# R107A.net
KiCad netlist of a schematic drawn in EAGLE
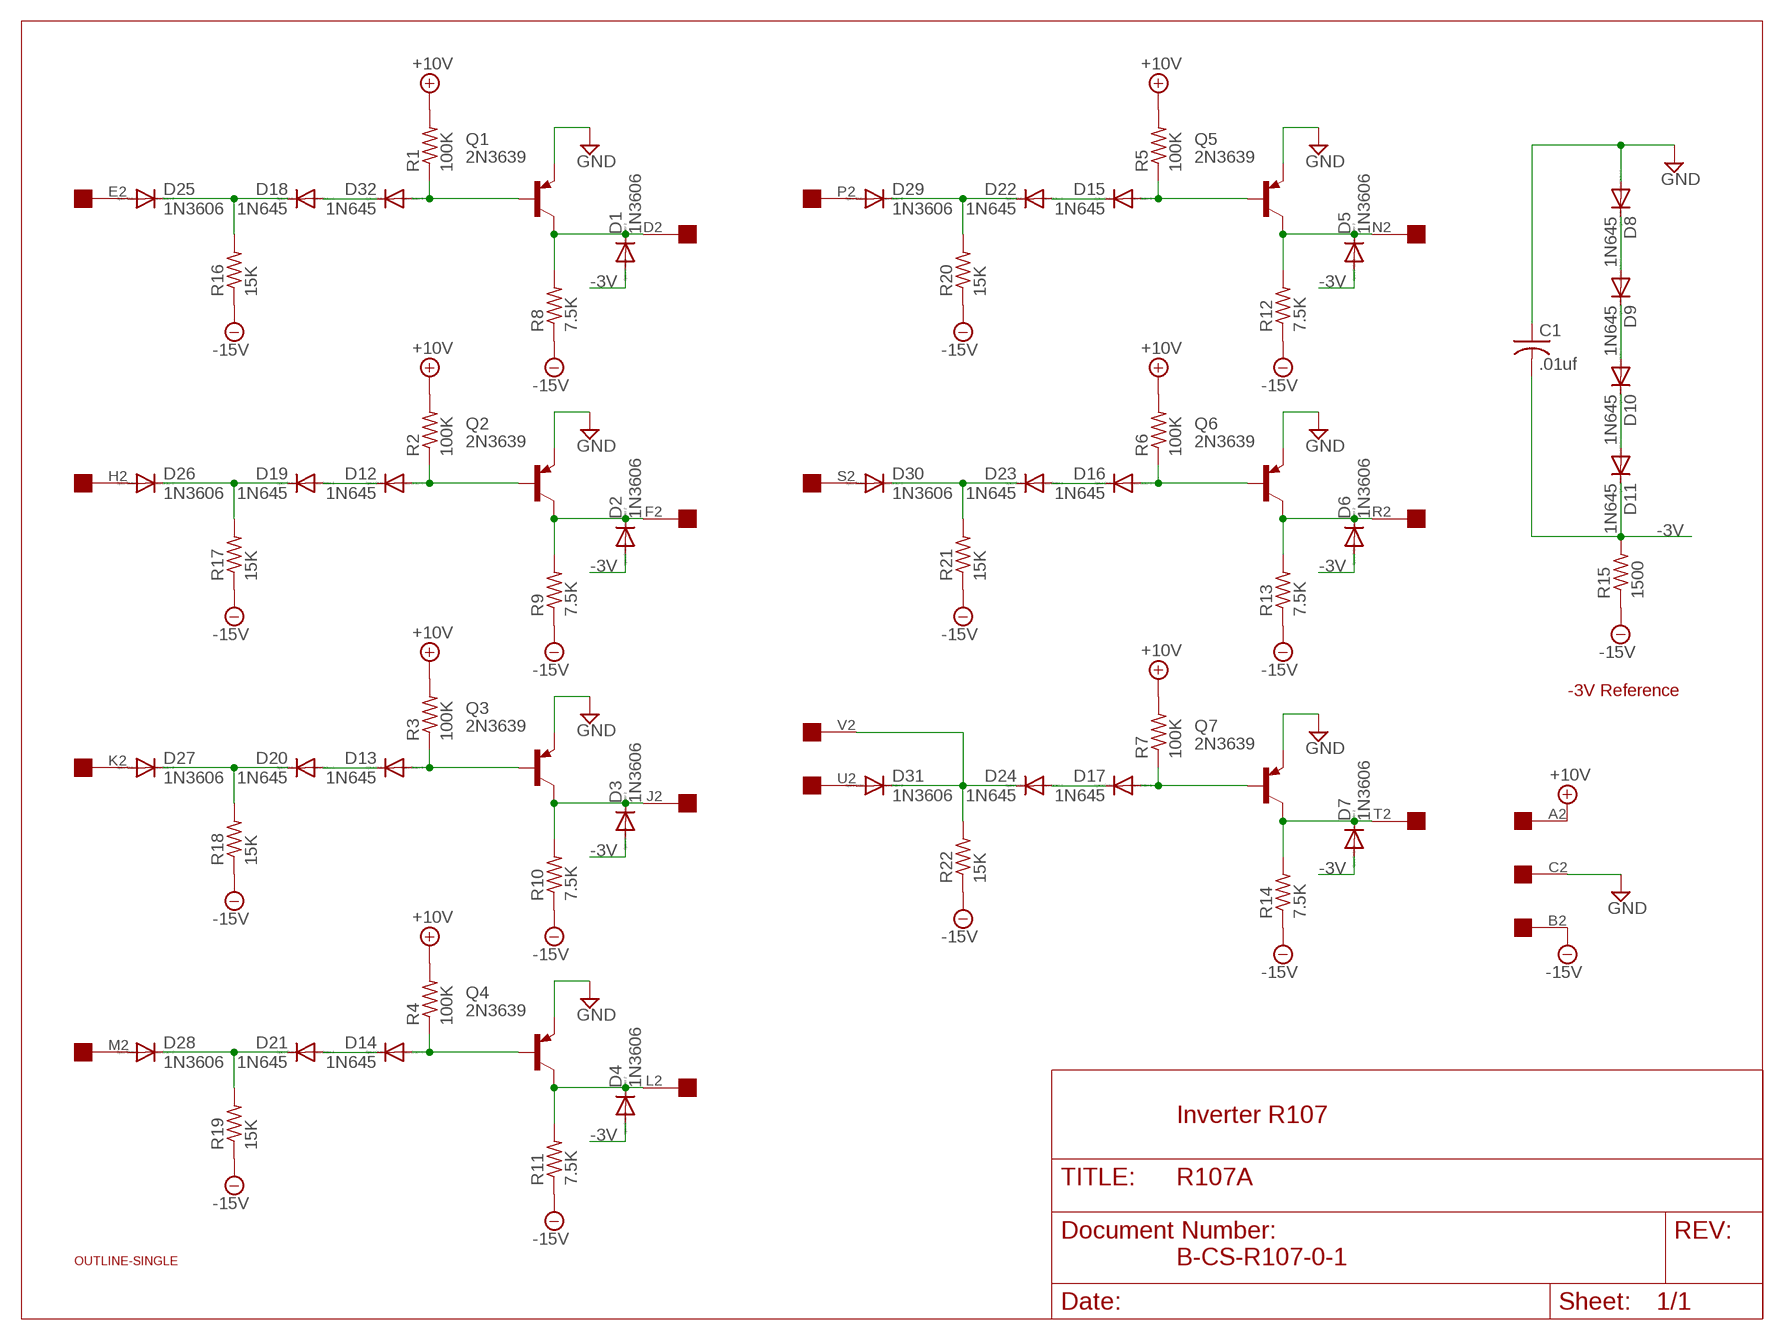
[diagram p0: schematic, sheet 1]

(export (version "E")
  (design (tool "Eeschema 10.0.6"))
  (components
    (comp (ref "C1")
      (value ".01uf")
      (footprint "eagle-import:C050-025X075")
      (libsource (lib "eagle-import") (part "C-US050-025X075"))
    )
    (comp (ref "D1")
      (value "1N3606")
      (footprint "eagle-import:DO35-10")
      (libsource (lib "eagle-import") (part "1N4148DO35-10"))
    )
    (comp (ref "D2")
      (value "1N3606")
      (footprint "eagle-import:DO35-10")
      (libsource (lib "eagle-import") (part "1N4148DO35-10"))
    )
    (comp (ref "D3")
      (value "1N3606")
      (footprint "eagle-import:DO35-10")
      (libsource (lib "eagle-import") (part "1N4148DO35-10"))
    )
    (comp (ref "D4")
      (value "1N3606")
      (footprint "eagle-import:DO35-10")
      (libsource (lib "eagle-import") (part "1N4148DO35-10"))
    )
    (comp (ref "D5")
      (value "1N3606")
      (footprint "eagle-import:DO35-10")
      (libsource (lib "eagle-import") (part "1N4148DO35-10"))
    )
    (comp (ref "D6")
      (value "1N3606")
      (footprint "eagle-import:DO35-10")
      (libsource (lib "eagle-import") (part "1N4148DO35-10"))
    )
    (comp (ref "D7")
      (value "1N3606")
      (footprint "eagle-import:DO35-10")
      (libsource (lib "eagle-import") (part "1N4148DO35-10"))
    )
    (comp (ref "D8")
      (value "1N645")
      (footprint "eagle-import:DO35-10")
      (libsource (lib "eagle-import") (part "1N4148DO35-10"))
    )
    (comp (ref "D9")
      (value "1N645")
      (footprint "eagle-import:DO35-10")
      (libsource (lib "eagle-import") (part "1N4148DO35-10"))
    )
    (comp (ref "D10")
      (value "1N645")
      (footprint "eagle-import:DO35-10")
      (libsource (lib "eagle-import") (part "1N4148DO35-10"))
    )
    (comp (ref "D11")
      (value "1N645")
      (footprint "eagle-import:DO35-10")
      (libsource (lib "eagle-import") (part "1N4148DO35-10"))
    )
    (comp (ref "D12")
      (value "1N645")
      (footprint "eagle-import:DO35-10")
      (libsource (lib "eagle-import") (part "1N4148DO35-10"))
    )
    (comp (ref "D13")
      (value "1N645")
      (footprint "eagle-import:DO35-10")
      (libsource (lib "eagle-import") (part "1N4148DO35-10"))
    )
    (comp (ref "D14")
      (value "1N645")
      (footprint "eagle-import:DO35-10")
      (libsource (lib "eagle-import") (part "1N4148DO35-10"))
    )
    (comp (ref "D15")
      (value "1N645")
      (footprint "eagle-import:DO35-10")
      (libsource (lib "eagle-import") (part "1N4148DO35-10"))
    )
    (comp (ref "D16")
      (value "1N645")
      (footprint "eagle-import:DO35-10")
      (libsource (lib "eagle-import") (part "1N4148DO35-10"))
    )
    (comp (ref "D17")
      (value "1N645")
      (footprint "eagle-import:DO35-10")
      (libsource (lib "eagle-import") (part "1N4148DO35-10"))
    )
    (comp (ref "D18")
      (value "1N645")
      (footprint "eagle-import:DO35-10")
      (libsource (lib "eagle-import") (part "1N4148DO35-10"))
    )
    (comp (ref "D19")
      (value "1N645")
      (footprint "eagle-import:DO35-10")
      (libsource (lib "eagle-import") (part "1N4148DO35-10"))
    )
    (comp (ref "D20")
      (value "1N645")
      (footprint "eagle-import:DO35-10")
      (libsource (lib "eagle-import") (part "1N4148DO35-10"))
    )
    (comp (ref "D21")
      (value "1N645")
      (footprint "eagle-import:DO35-10")
      (libsource (lib "eagle-import") (part "1N4148DO35-10"))
    )
    (comp (ref "D22")
      (value "1N645")
      (footprint "eagle-import:DO35-10")
      (libsource (lib "eagle-import") (part "1N4148DO35-10"))
    )
    (comp (ref "D23")
      (value "1N645")
      (footprint "eagle-import:DO35-10")
      (libsource (lib "eagle-import") (part "1N4148DO35-10"))
    )
    (comp (ref "D24")
      (value "1N645")
      (footprint "eagle-import:DO35-10")
      (libsource (lib "eagle-import") (part "1N4148DO35-10"))
    )
    (comp (ref "D25")
      (value "1N3606")
      (footprint "eagle-import:DO35-10")
      (libsource (lib "eagle-import") (part "1N4148DO35-10"))
    )
    (comp (ref "D26")
      (value "1N3606")
      (footprint "eagle-import:DO35-10")
      (libsource (lib "eagle-import") (part "1N4148DO35-10"))
    )
    (comp (ref "D27")
      (value "1N3606")
      (footprint "eagle-import:DO35-10")
      (libsource (lib "eagle-import") (part "1N4148DO35-10"))
    )
    (comp (ref "D28")
      (value "1N3606")
      (footprint "eagle-import:DO35-10")
      (libsource (lib "eagle-import") (part "1N4148DO35-10"))
    )
    (comp (ref "D29")
      (value "1N3606")
      (footprint "eagle-import:DO35-10")
      (libsource (lib "eagle-import") (part "1N4148DO35-10"))
    )
    (comp (ref "D30")
      (value "1N3606")
      (footprint "eagle-import:DO35-10")
      (libsource (lib "eagle-import") (part "1N4148DO35-10"))
    )
    (comp (ref "D31")
      (value "1N3606")
      (footprint "eagle-import:DO35-10")
      (libsource (lib "eagle-import") (part "1N4148DO35-10"))
    )
    (comp (ref "D32")
      (value "1N645")
      (footprint "eagle-import:DO35-10")
      (libsource (lib "eagle-import") (part "1N4148DO35-10"))
    )
    (comp (ref "Q1")
      (value "2N3639")
      (footprint "eagle-import:TO39")
      (libsource (lib "eagle-import") (part "2N3637"))
    )
    (comp (ref "Q2")
      (value "2N3639")
      (footprint "eagle-import:TO39")
      (libsource (lib "eagle-import") (part "2N3637"))
    )
    (comp (ref "Q3")
      (value "2N3639")
      (footprint "eagle-import:TO39")
      (libsource (lib "eagle-import") (part "2N3637"))
    )
    (comp (ref "Q4")
      (value "2N3639")
      (footprint "eagle-import:TO39")
      (libsource (lib "eagle-import") (part "2N3637"))
    )
    (comp (ref "Q5")
      (value "2N3639")
      (footprint "eagle-import:TO39")
      (libsource (lib "eagle-import") (part "2N3637"))
    )
    (comp (ref "Q6")
      (value "2N3639")
      (footprint "eagle-import:TO39")
      (libsource (lib "eagle-import") (part "2N3637"))
    )
    (comp (ref "Q7")
      (value "2N3639")
      (footprint "eagle-import:TO39")
      (libsource (lib "eagle-import") (part "2N3637"))
    )
    (comp (ref "R1")
      (value "100K")
      (footprint "eagle-import:0207_10")
      (libsource (lib "eagle-import") (part "R-US_0207/10"))
    )
    (comp (ref "R2")
      (value "100K")
      (footprint "eagle-import:0207_10")
      (libsource (lib "eagle-import") (part "R-US_0207/10"))
    )
    (comp (ref "R3")
      (value "100K")
      (footprint "eagle-import:0207_10")
      (libsource (lib "eagle-import") (part "R-US_0207/10"))
    )
    (comp (ref "R4")
      (value "100K")
      (footprint "eagle-import:0207_10")
      (libsource (lib "eagle-import") (part "R-US_0207/10"))
    )
    (comp (ref "R5")
      (value "100K")
      (footprint "eagle-import:0207_10")
      (libsource (lib "eagle-import") (part "R-US_0207/10"))
    )
    (comp (ref "R6")
      (value "100K")
      (footprint "eagle-import:0207_10")
      (libsource (lib "eagle-import") (part "R-US_0207/10"))
    )
    (comp (ref "R7")
      (value "100K")
      (footprint "eagle-import:0207_10")
      (libsource (lib "eagle-import") (part "R-US_0207/10"))
    )
    (comp (ref "R8")
      (value "7.5K")
      (footprint "eagle-import:0207_10")
      (libsource (lib "eagle-import") (part "R-US_0207/10"))
    )
    (comp (ref "R9")
      (value "7.5K")
      (footprint "eagle-import:0207_10")
      (libsource (lib "eagle-import") (part "R-US_0207/10"))
    )
    (comp (ref "R10")
      (value "7.5K")
      (footprint "eagle-import:0207_10")
      (libsource (lib "eagle-import") (part "R-US_0207/10"))
    )
    (comp (ref "R11")
      (value "7.5K")
      (footprint "eagle-import:0207_10")
      (libsource (lib "eagle-import") (part "R-US_0207/10"))
    )
    (comp (ref "R12")
      (value "7.5K")
      (footprint "eagle-import:0207_10")
      (libsource (lib "eagle-import") (part "R-US_0207/10"))
    )
    (comp (ref "R13")
      (value "7.5K")
      (footprint "eagle-import:0207_10")
      (libsource (lib "eagle-import") (part "R-US_0207/10"))
    )
    (comp (ref "R14")
      (value "7.5K")
      (footprint "eagle-import:0207_10")
      (libsource (lib "eagle-import") (part "R-US_0207/10"))
    )
    (comp (ref "R15")
      (value "1500")
      (footprint "eagle-import:0207_10")
      (libsource (lib "eagle-import") (part "R-US_0207/10"))
    )
    (comp (ref "R16")
      (value "15K")
      (footprint "eagle-import:0207_10")
      (libsource (lib "eagle-import") (part "R-US_0207/10"))
    )
    (comp (ref "R17")
      (value "15K")
      (footprint "eagle-import:0207_10")
      (libsource (lib "eagle-import") (part "R-US_0207/10"))
    )
    (comp (ref "R18")
      (value "15K")
      (footprint "eagle-import:0207_10")
      (libsource (lib "eagle-import") (part "R-US_0207/10"))
    )
    (comp (ref "R19")
      (value "15K")
      (footprint "eagle-import:0207_10")
      (libsource (lib "eagle-import") (part "R-US_0207/10"))
    )
    (comp (ref "R20")
      (value "15K")
      (footprint "eagle-import:0207_10")
      (libsource (lib "eagle-import") (part "R-US_0207/10"))
    )
    (comp (ref "R21")
      (value "15K")
      (footprint "eagle-import:0207_10")
      (libsource (lib "eagle-import") (part "R-US_0207/10"))
    )
    (comp (ref "R22")
      (value "15K")
      (footprint "eagle-import:0207_10")
      (libsource (lib "eagle-import") (part "R-US_0207/10"))
    )
    (comp (ref "U$1")
      (value "OUTLINE-SINGLE")
      (footprint "eagle-import:SINGLE")
      (libsource (lib "eagle-import") (part "OUTLINE-SINGLE"))
    )
    (comp (ref "U$2")
      (value "EDGE-1")
      (footprint "eagle-import:EDGE-CON1")
      (libsource (lib "eagle-import") (part "EDGE-1"))
    )
  )
  (nets
    (net (code "1") (name "+10V") (class "Default")
      (node (ref "R1") (pin "2") (pinfunction "2_2") (pintype "passive"))
      (node (ref "R2") (pin "2") (pinfunction "2_2") (pintype "passive"))
      (node (ref "R3") (pin "2") (pinfunction "2_2") (pintype "passive"))
      (node (ref "R4") (pin "2") (pinfunction "2_2") (pintype "passive"))
      (node (ref "R5") (pin "2") (pinfunction "2_2") (pintype "passive"))
      (node (ref "R6") (pin "2") (pinfunction "2_2") (pintype "passive"))
      (node (ref "R7") (pin "2") (pinfunction "2_2") (pintype "passive"))
      (node (ref "U$2") (pin "A2") (pinfunction "1_A2") (pintype "bidirectional"))
    )
    (net (code "2") (name "-15V") (class "Default")
      (node (ref "R10") (pin "1") (pinfunction "1_1") (pintype "passive"))
      (node (ref "R11") (pin "1") (pinfunction "1_1") (pintype "passive"))
      (node (ref "R12") (pin "1") (pinfunction "1_1") (pintype "passive"))
      (node (ref "R13") (pin "1") (pinfunction "1_1") (pintype "passive"))
      (node (ref "R14") (pin "1") (pinfunction "1_1") (pintype "passive"))
      (node (ref "R15") (pin "1") (pinfunction "1_1") (pintype "passive"))
      (node (ref "R16") (pin "1") (pinfunction "1_1") (pintype "passive"))
      (node (ref "R17") (pin "1") (pinfunction "1_1") (pintype "passive"))
      (node (ref "R18") (pin "1") (pinfunction "1_1") (pintype "passive"))
      (node (ref "R19") (pin "1") (pinfunction "1_1") (pintype "passive"))
      (node (ref "R20") (pin "1") (pinfunction "1_1") (pintype "passive"))
      (node (ref "R21") (pin "1") (pinfunction "1_1") (pintype "passive"))
      (node (ref "R22") (pin "1") (pinfunction "1_1") (pintype "passive"))
      (node (ref "R8") (pin "1") (pinfunction "1_1") (pintype "passive"))
      (node (ref "R9") (pin "1") (pinfunction "1_1") (pintype "passive"))
      (node (ref "U$2") (pin "B2") (pinfunction "1_B2") (pintype "bidirectional"))
    )
    (net (code "3") (name "/-3V") (class "Default")
      (node (ref "C1") (pin "2") (pinfunction "2_2") (pintype "passive"))
      (node (ref "D1") (pin "A") (pinfunction "A_A") (pintype "passive"))
      (node (ref "D11") (pin "C") (pinfunction "C_C") (pintype "passive"))
      (node (ref "D2") (pin "A") (pinfunction "A_A") (pintype "passive"))
      (node (ref "D3") (pin "A") (pinfunction "A_A") (pintype "passive"))
      (node (ref "D4") (pin "A") (pinfunction "A_A") (pintype "passive"))
      (node (ref "D5") (pin "A") (pinfunction "A_A") (pintype "passive"))
      (node (ref "D6") (pin "A") (pinfunction "A_A") (pintype "passive"))
      (node (ref "D7") (pin "A") (pinfunction "A_A") (pintype "passive"))
      (node (ref "R15") (pin "2") (pinfunction "2_2") (pintype "passive"))
    )
    (net (code "4") (name "GND") (class "Default")
      (node (ref "C1") (pin "1") (pinfunction "1_1") (pintype "passive"))
      (node (ref "D8") (pin "A") (pinfunction "A_A") (pintype "passive"))
      (node (ref "Q1") (pin "1") (pinfunction "E_1") (pintype "passive"))
      (node (ref "Q2") (pin "1") (pinfunction "E_1") (pintype "passive"))
      (node (ref "Q3") (pin "1") (pinfunction "E_1") (pintype "passive"))
      (node (ref "Q4") (pin "1") (pinfunction "E_1") (pintype "passive"))
      (node (ref "Q5") (pin "1") (pinfunction "E_1") (pintype "passive"))
      (node (ref "Q6") (pin "1") (pinfunction "E_1") (pintype "passive"))
      (node (ref "Q7") (pin "1") (pinfunction "E_1") (pintype "passive"))
      (node (ref "U$2") (pin "C2") (pinfunction "1_C2") (pintype "bidirectional"))
    )
    (net (code "5") (name "Net-(D8-PadC)") (class "Default")
      (node (ref "D8") (pin "C") (pinfunction "C_C") (pintype "passive"))
      (node (ref "D9") (pin "A") (pinfunction "A_A") (pintype "passive"))
    )
    (net (code "6") (name "Net-(D10-PadA)") (class "Default")
      (node (ref "D10") (pin "A") (pinfunction "A_A") (pintype "passive"))
      (node (ref "D9") (pin "C") (pinfunction "C_C") (pintype "passive"))
    )
    (net (code "7") (name "Net-(D10-PadC)") (class "Default")
      (node (ref "D10") (pin "C") (pinfunction "C_C") (pintype "passive"))
      (node (ref "D11") (pin "A") (pinfunction "A_A") (pintype "passive"))
    )
    (net (code "8") (name "Net-(D12-PadC)") (class "Default")
      (node (ref "D12") (pin "C") (pinfunction "C_C") (pintype "passive"))
      (node (ref "D19") (pin "A") (pinfunction "A_A") (pintype "passive"))
    )
    (net (code "9") (name "Net-(D13-PadC)") (class "Default")
      (node (ref "D13") (pin "C") (pinfunction "C_C") (pintype "passive"))
      (node (ref "D20") (pin "A") (pinfunction "A_A") (pintype "passive"))
    )
    (net (code "10") (name "Net-(D14-PadC)") (class "Default")
      (node (ref "D14") (pin "C") (pinfunction "C_C") (pintype "passive"))
      (node (ref "D21") (pin "A") (pinfunction "A_A") (pintype "passive"))
    )
    (net (code "11") (name "Net-(D15-PadC)") (class "Default")
      (node (ref "D15") (pin "C") (pinfunction "C_C") (pintype "passive"))
      (node (ref "D22") (pin "A") (pinfunction "A_A") (pintype "passive"))
    )
    (net (code "12") (name "Net-(D16-PadC)") (class "Default")
      (node (ref "D16") (pin "C") (pinfunction "C_C") (pintype "passive"))
      (node (ref "D23") (pin "A") (pinfunction "A_A") (pintype "passive"))
    )
    (net (code "13") (name "Net-(D17-PadC)") (class "Default")
      (node (ref "D17") (pin "C") (pinfunction "C_C") (pintype "passive"))
      (node (ref "D24") (pin "A") (pinfunction "A_A") (pintype "passive"))
    )
    (net (code "14") (name "Net-(D18-PadA)") (class "Default")
      (node (ref "D18") (pin "A") (pinfunction "A_A") (pintype "passive"))
      (node (ref "D32") (pin "C") (pinfunction "C_C") (pintype "passive"))
    )
    (net (code "15") (name "Net-(D18-PadC)") (class "Default")
      (node (ref "D18") (pin "C") (pinfunction "C_C") (pintype "passive"))
      (node (ref "D25") (pin "C") (pinfunction "C_C") (pintype "passive"))
      (node (ref "R16") (pin "2") (pinfunction "2_2") (pintype "passive"))
    )
    (net (code "16") (name "Net-(D19-PadC)") (class "Default")
      (node (ref "D19") (pin "C") (pinfunction "C_C") (pintype "passive"))
      (node (ref "D26") (pin "C") (pinfunction "C_C") (pintype "passive"))
      (node (ref "R17") (pin "2") (pinfunction "2_2") (pintype "passive"))
    )
    (net (code "17") (name "Net-(D20-PadC)") (class "Default")
      (node (ref "D20") (pin "C") (pinfunction "C_C") (pintype "passive"))
      (node (ref "D27") (pin "C") (pinfunction "C_C") (pintype "passive"))
      (node (ref "R18") (pin "2") (pinfunction "2_2") (pintype "passive"))
    )
    (net (code "18") (name "Net-(D21-PadC)") (class "Default")
      (node (ref "D21") (pin "C") (pinfunction "C_C") (pintype "passive"))
      (node (ref "D28") (pin "C") (pinfunction "C_C") (pintype "passive"))
      (node (ref "R19") (pin "2") (pinfunction "2_2") (pintype "passive"))
    )
    (net (code "19") (name "Net-(D22-PadC)") (class "Default")
      (node (ref "D22") (pin "C") (pinfunction "C_C") (pintype "passive"))
      (node (ref "D29") (pin "C") (pinfunction "C_C") (pintype "passive"))
      (node (ref "R20") (pin "2") (pinfunction "2_2") (pintype "passive"))
    )
    (net (code "20") (name "Net-(D23-PadC)") (class "Default")
      (node (ref "D23") (pin "C") (pinfunction "C_C") (pintype "passive"))
      (node (ref "D30") (pin "C") (pinfunction "C_C") (pintype "passive"))
      (node (ref "R21") (pin "2") (pinfunction "2_2") (pintype "passive"))
    )
    (net (code "21") (name "Net-(Q1-B)") (class "Default")
      (node (ref "D32") (pin "A") (pinfunction "A_A") (pintype "passive"))
      (node (ref "Q1") (pin "2") (pinfunction "B_2") (pintype "passive"))
      (node (ref "R1") (pin "1") (pinfunction "1_1") (pintype "passive"))
    )
    (net (code "22") (name "Net-(Q1-C)") (class "Default")
      (node (ref "D1") (pin "C") (pinfunction "C_C") (pintype "passive"))
      (node (ref "Q1") (pin "3") (pinfunction "C_3") (pintype "passive"))
      (node (ref "R8") (pin "2") (pinfunction "2_2") (pintype "passive"))
      (node (ref "U$2") (pin "D2") (pinfunction "1_D2") (pintype "bidirectional"))
    )
    (net (code "23") (name "Net-(Q2-B)") (class "Default")
      (node (ref "D12") (pin "A") (pinfunction "A_A") (pintype "passive"))
      (node (ref "Q2") (pin "2") (pinfunction "B_2") (pintype "passive"))
      (node (ref "R2") (pin "1") (pinfunction "1_1") (pintype "passive"))
    )
    (net (code "24") (name "Net-(Q2-C)") (class "Default")
      (node (ref "D2") (pin "C") (pinfunction "C_C") (pintype "passive"))
      (node (ref "Q2") (pin "3") (pinfunction "C_3") (pintype "passive"))
      (node (ref "R9") (pin "2") (pinfunction "2_2") (pintype "passive"))
      (node (ref "U$2") (pin "F2") (pinfunction "1_F2") (pintype "bidirectional"))
    )
    (net (code "25") (name "Net-(Q3-B)") (class "Default")
      (node (ref "D13") (pin "A") (pinfunction "A_A") (pintype "passive"))
      (node (ref "Q3") (pin "2") (pinfunction "B_2") (pintype "passive"))
      (node (ref "R3") (pin "1") (pinfunction "1_1") (pintype "passive"))
    )
    (net (code "26") (name "Net-(Q3-C)") (class "Default")
      (node (ref "D3") (pin "C") (pinfunction "C_C") (pintype "passive"))
      (node (ref "Q3") (pin "3") (pinfunction "C_3") (pintype "passive"))
      (node (ref "R10") (pin "2") (pinfunction "2_2") (pintype "passive"))
      (node (ref "U$2") (pin "J2") (pinfunction "1_J2") (pintype "bidirectional"))
    )
    (net (code "27") (name "Net-(Q4-B)") (class "Default")
      (node (ref "D14") (pin "A") (pinfunction "A_A") (pintype "passive"))
      (node (ref "Q4") (pin "2") (pinfunction "B_2") (pintype "passive"))
      (node (ref "R4") (pin "1") (pinfunction "1_1") (pintype "passive"))
    )
    (net (code "28") (name "Net-(Q4-C)") (class "Default")
      (node (ref "D4") (pin "C") (pinfunction "C_C") (pintype "passive"))
      (node (ref "Q4") (pin "3") (pinfunction "C_3") (pintype "passive"))
      (node (ref "R11") (pin "2") (pinfunction "2_2") (pintype "passive"))
      (node (ref "U$2") (pin "L2") (pinfunction "1_L2") (pintype "bidirectional"))
    )
    (net (code "29") (name "Net-(Q5-B)") (class "Default")
      (node (ref "D15") (pin "A") (pinfunction "A_A") (pintype "passive"))
      (node (ref "Q5") (pin "2") (pinfunction "B_2") (pintype "passive"))
      (node (ref "R5") (pin "1") (pinfunction "1_1") (pintype "passive"))
    )
    (net (code "30") (name "Net-(Q5-C)") (class "Default")
      (node (ref "D5") (pin "C") (pinfunction "C_C") (pintype "passive"))
      (node (ref "Q5") (pin "3") (pinfunction "C_3") (pintype "passive"))
      (node (ref "R12") (pin "2") (pinfunction "2_2") (pintype "passive"))
      (node (ref "U$2") (pin "N2") (pinfunction "1_N2") (pintype "bidirectional"))
    )
    (net (code "31") (name "Net-(Q6-B)") (class "Default")
      (node (ref "D16") (pin "A") (pinfunction "A_A") (pintype "passive"))
      (node (ref "Q6") (pin "2") (pinfunction "B_2") (pintype "passive"))
      (node (ref "R6") (pin "1") (pinfunction "1_1") (pintype "passive"))
    )
    (net (code "32") (name "Net-(Q6-C)") (class "Default")
      (node (ref "D6") (pin "C") (pinfunction "C_C") (pintype "passive"))
      (node (ref "Q6") (pin "3") (pinfunction "C_3") (pintype "passive"))
      (node (ref "R13") (pin "2") (pinfunction "2_2") (pintype "passive"))
      (node (ref "U$2") (pin "R2") (pinfunction "1_R2") (pintype "bidirectional"))
    )
    (net (code "33") (name "Net-(Q7-B)") (class "Default")
      (node (ref "D17") (pin "A") (pinfunction "A_A") (pintype "passive"))
      (node (ref "Q7") (pin "2") (pinfunction "B_2") (pintype "passive"))
      (node (ref "R7") (pin "1") (pinfunction "1_1") (pintype "passive"))
    )
    (net (code "34") (name "Net-(Q7-C)") (class "Default")
      (node (ref "D7") (pin "C") (pinfunction "C_C") (pintype "passive"))
      (node (ref "Q7") (pin "3") (pinfunction "C_3") (pintype "passive"))
      (node (ref "R14") (pin "2") (pinfunction "2_2") (pintype "passive"))
      (node (ref "U$2") (pin "T2") (pinfunction "1_T2") (pintype "bidirectional"))
    )
    (net (code "35") (name "Net-(U$2E-1)") (class "Default")
      (node (ref "D25") (pin "A") (pinfunction "A_A") (pintype "passive"))
      (node (ref "U$2") (pin "E2") (pinfunction "1_E2") (pintype "bidirectional"))
    )
    (net (code "36") (name "Net-(U$2G-1)") (class "Default")
      (node (ref "D26") (pin "A") (pinfunction "A_A") (pintype "passive"))
      (node (ref "U$2") (pin "H2") (pinfunction "1_H2") (pintype "bidirectional"))
    )
    (net (code "37") (name "Net-(U$2I-1)") (class "Default")
      (node (ref "D27") (pin "A") (pinfunction "A_A") (pintype "passive"))
      (node (ref "U$2") (pin "K2") (pinfunction "1_K2") (pintype "bidirectional"))
    )
    (net (code "38") (name "Net-(U$2K-1)") (class "Default")
      (node (ref "D28") (pin "A") (pinfunction "A_A") (pintype "passive"))
      (node (ref "U$2") (pin "M2") (pinfunction "1_M2") (pintype "bidirectional"))
    )
    (net (code "39") (name "Net-(U$2M-1)") (class "Default")
      (node (ref "D29") (pin "A") (pinfunction "A_A") (pintype "passive"))
      (node (ref "U$2") (pin "P2") (pinfunction "1_P2") (pintype "bidirectional"))
    )
    (net (code "40") (name "Net-(U$2O-1)") (class "Default")
      (node (ref "D30") (pin "A") (pinfunction "A_A") (pintype "passive"))
      (node (ref "U$2") (pin "S2") (pinfunction "1_S2") (pintype "bidirectional"))
    )
    (net (code "41") (name "Net-(U$2Q-1)") (class "Default")
      (node (ref "D31") (pin "A") (pinfunction "A_A") (pintype "passive"))
      (node (ref "U$2") (pin "U2") (pinfunction "1_U2") (pintype "bidirectional"))
    )
    (net (code "42") (name "Net-(U$2R-1)") (class "Default")
      (node (ref "D24") (pin "C") (pinfunction "C_C") (pintype "passive"))
      (node (ref "D31") (pin "C") (pinfunction "C_C") (pintype "passive"))
      (node (ref "R22") (pin "2") (pinfunction "2_2") (pintype "passive"))
      (node (ref "U$2") (pin "V2") (pinfunction "1_V2") (pintype "bidirectional"))
    )
  )
)
